# TPS.net
KiCad netlist of a schematic drawn in EAGLE
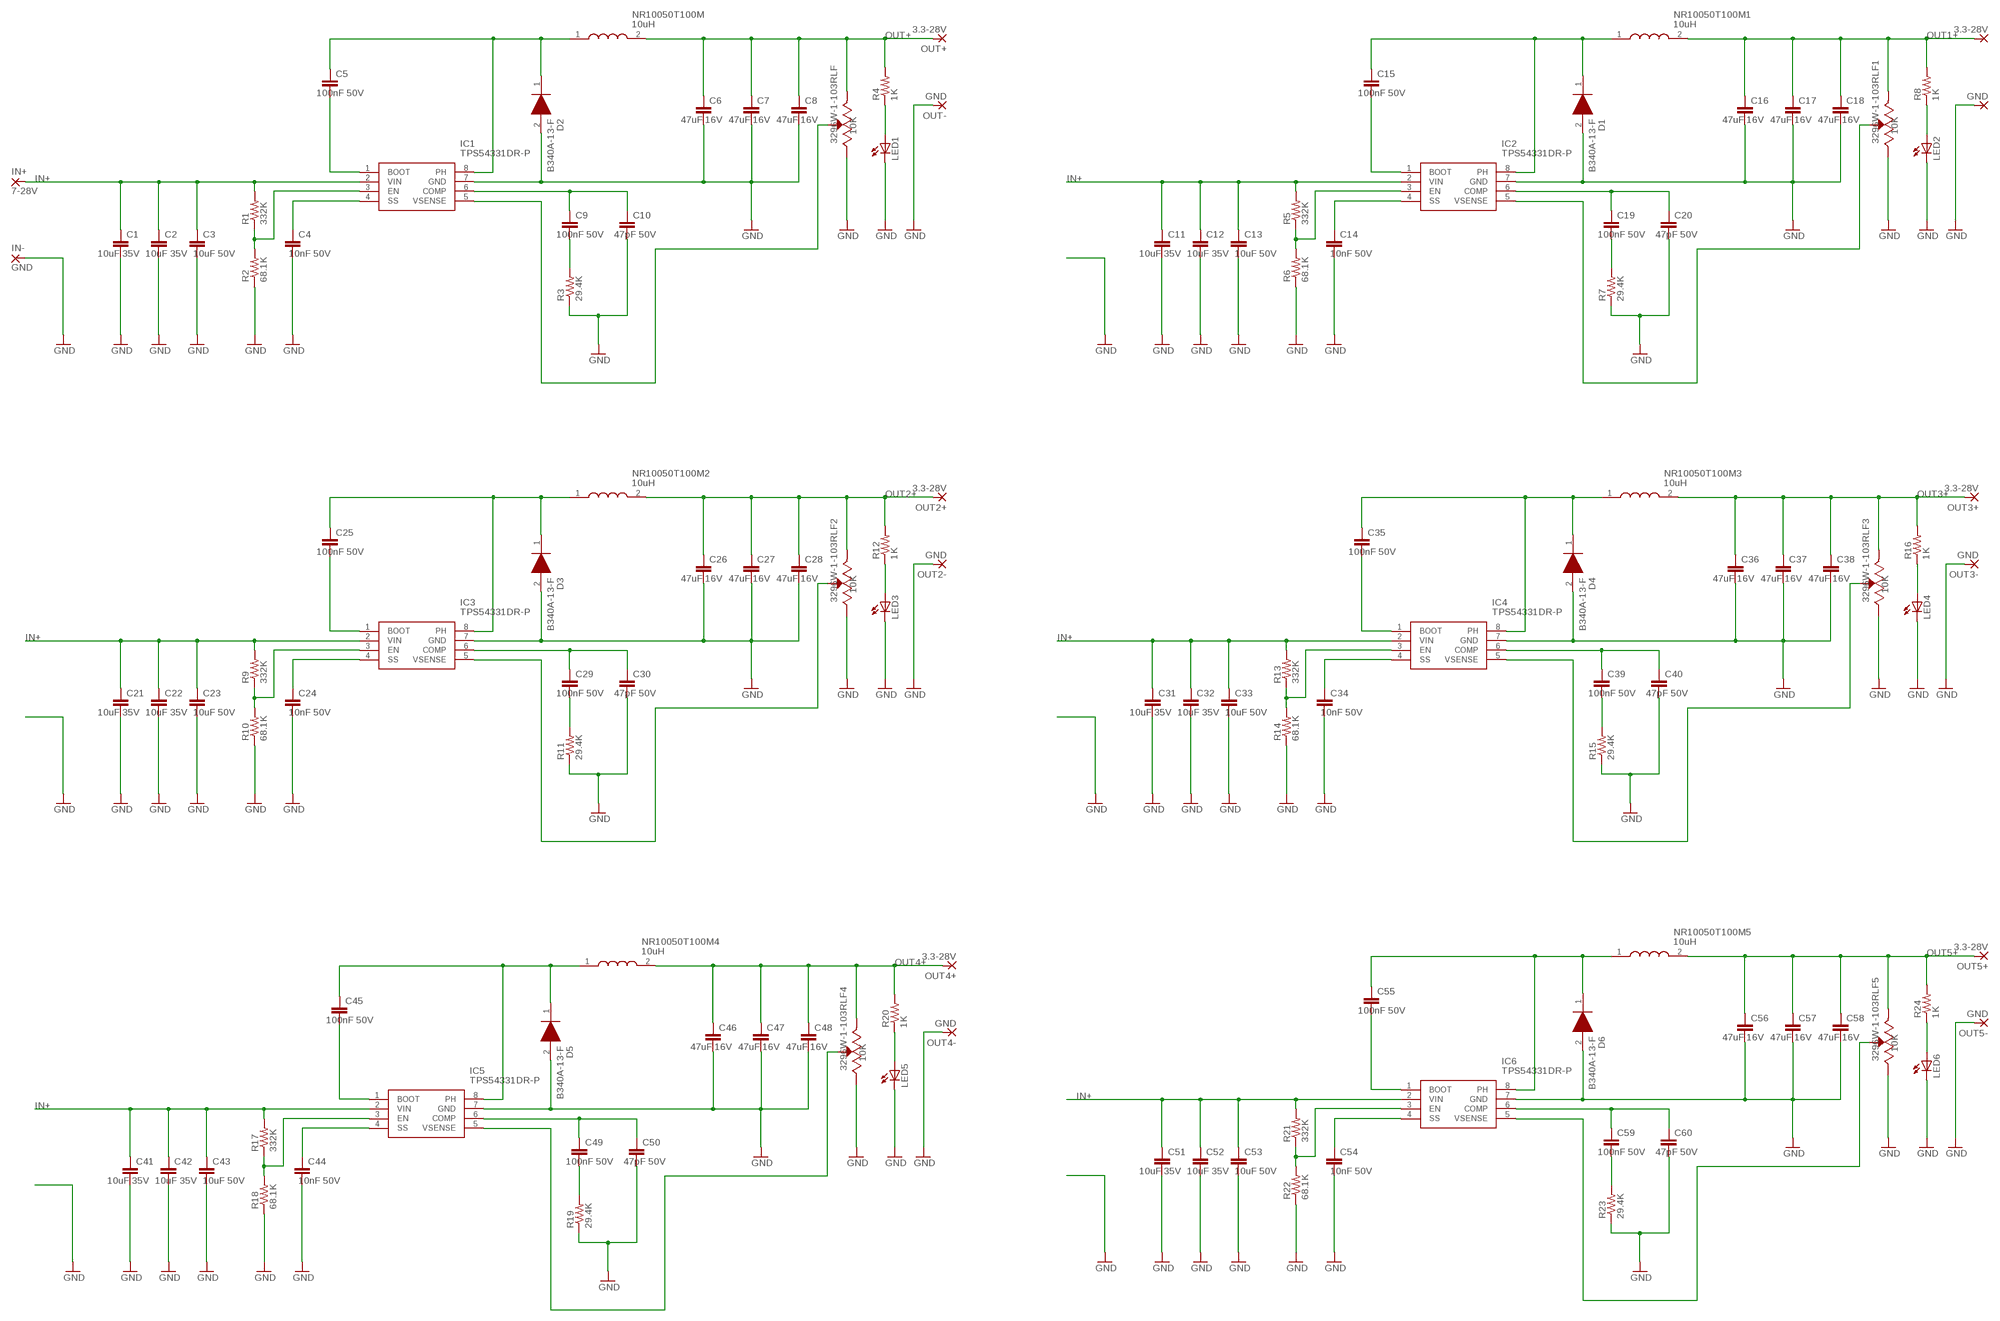
[diagram p0: schematic, sheet 1]

(export (version "E")
  (design (tool "Eeschema 10.0.6"))
  (components
    (comp (ref "3296W-1-103RLF")
      (value "10K")
      (footprint "eagle-import:TRIM_3296W-1-103RLF")
      (fields (field (name "MF") "Bourns") (field (name "MP") "3296W-1-103RLF"))
      (libsource (lib "eagle-import") (part "3296W-1-103RLF"))
    )
    (comp (ref "3296W-1-103RLF1")
      (value "10K")
      (footprint "eagle-import:TRIM_3296W-1-103RLF")
      (fields (field (name "MF") "Bourns") (field (name "MP") "3296W-1-103RLF"))
      (libsource (lib "eagle-import") (part "3296W-1-103RLF"))
    )
    (comp (ref "3296W-1-103RLF2")
      (value "10K")
      (footprint "eagle-import:TRIM_3296W-1-103RLF")
      (fields (field (name "MF") "Bourns") (field (name "MP") "3296W-1-103RLF"))
      (libsource (lib "eagle-import") (part "3296W-1-103RLF"))
    )
    (comp (ref "3296W-1-103RLF3")
      (value "10K")
      (footprint "eagle-import:TRIM_3296W-1-103RLF")
      (fields (field (name "MF") "Bourns") (field (name "MP") "3296W-1-103RLF"))
      (libsource (lib "eagle-import") (part "3296W-1-103RLF"))
    )
    (comp (ref "3296W-1-103RLF4")
      (value "10K")
      (footprint "eagle-import:TRIM_3296W-1-103RLF")
      (fields (field (name "MF") "Bourns") (field (name "MP") "3296W-1-103RLF"))
      (libsource (lib "eagle-import") (part "3296W-1-103RLF"))
    )
    (comp (ref "3296W-1-103RLF5")
      (value "10K")
      (footprint "eagle-import:TRIM_3296W-1-103RLF")
      (fields (field (name "MF") "Bourns") (field (name "MP") "3296W-1-103RLF"))
      (libsource (lib "eagle-import") (part "3296W-1-103RLF"))
    )
    (comp (ref "C1")
      (value "10uF 35V")
      (footprint "eagle-import:SPARKFUN_1206")
      (libsource (lib "eagle-import") (part "SPARKFUN_CAP1206"))
    )
    (comp (ref "C2")
      (value "10uF 35V")
      (footprint "eagle-import:SPARKFUN_1206")
      (libsource (lib "eagle-import") (part "SPARKFUN_CAP1206"))
    )
    (comp (ref "C3")
      (value "10uF 50V")
      (footprint "eagle-import:1206")
      (libsource (lib "eagle-import") (part "CAP1206"))
    )
    (comp (ref "C4")
      (value "10nF 50V")
      (footprint "eagle-import:SPARKFUN_1206")
      (libsource (lib "eagle-import") (part "SPARKFUN_CAP1206"))
    )
    (comp (ref "C5")
      (value "100nF 50V")
      (footprint "eagle-import:SPARKFUN_1206")
      (libsource (lib "eagle-import") (part "SPARKFUN_CAP1206"))
    )
    (comp (ref "C6")
      (value "47uF 16V")
      (footprint "eagle-import:SPARKFUN_1206")
      (libsource (lib "eagle-import") (part "SPARKFUN_CAP1206"))
    )
    (comp (ref "C7")
      (value "47uF 16V")
      (footprint "eagle-import:SPARKFUN_1206")
      (libsource (lib "eagle-import") (part "SPARKFUN_CAP1206"))
    )
    (comp (ref "C8")
      (value "47uF 16V")
      (footprint "eagle-import:SPARKFUN_1206")
      (libsource (lib "eagle-import") (part "SPARKFUN_CAP1206"))
    )
    (comp (ref "C9")
      (value "100nF 50V")
      (footprint "eagle-import:SPARKFUN_1206")
      (libsource (lib "eagle-import") (part "SPARKFUN_CAP1206"))
    )
    (comp (ref "C10")
      (value "47pF 50V")
      (footprint "eagle-import:SPARKFUN_1206")
      (libsource (lib "eagle-import") (part "SPARKFUN_CAP1206"))
    )
    (comp (ref "C11")
      (value "10uF 35V")
      (footprint "eagle-import:SPARKFUN_1206")
      (libsource (lib "eagle-import") (part "SPARKFUN_CAP1206"))
    )
    (comp (ref "C12")
      (value "10uF 35V")
      (footprint "eagle-import:SPARKFUN_1206")
      (libsource (lib "eagle-import") (part "SPARKFUN_CAP1206"))
    )
    (comp (ref "C13")
      (value "10uF 50V")
      (footprint "eagle-import:1206")
      (libsource (lib "eagle-import") (part "CAP1206"))
    )
    (comp (ref "C14")
      (value "10nF 50V")
      (footprint "eagle-import:SPARKFUN_1206")
      (libsource (lib "eagle-import") (part "SPARKFUN_CAP1206"))
    )
    (comp (ref "C15")
      (value "100nF 50V")
      (footprint "eagle-import:SPARKFUN_1206")
      (libsource (lib "eagle-import") (part "SPARKFUN_CAP1206"))
    )
    (comp (ref "C16")
      (value "47uF 16V")
      (footprint "eagle-import:SPARKFUN_1206")
      (libsource (lib "eagle-import") (part "SPARKFUN_CAP1206"))
    )
    (comp (ref "C17")
      (value "47uF 16V")
      (footprint "eagle-import:SPARKFUN_1206")
      (libsource (lib "eagle-import") (part "SPARKFUN_CAP1206"))
    )
    (comp (ref "C18")
      (value "47uF 16V")
      (footprint "eagle-import:SPARKFUN_1206")
      (libsource (lib "eagle-import") (part "SPARKFUN_CAP1206"))
    )
    (comp (ref "C19")
      (value "100nF 50V")
      (footprint "eagle-import:SPARKFUN_1206")
      (libsource (lib "eagle-import") (part "SPARKFUN_CAP1206"))
    )
    (comp (ref "C20")
      (value "47pF 50V")
      (footprint "eagle-import:SPARKFUN_1206")
      (libsource (lib "eagle-import") (part "SPARKFUN_CAP1206"))
    )
    (comp (ref "C21")
      (value "10uF 35V")
      (footprint "eagle-import:SPARKFUN_1206")
      (libsource (lib "eagle-import") (part "SPARKFUN_CAP1206"))
    )
    (comp (ref "C22")
      (value "10uF 35V")
      (footprint "eagle-import:SPARKFUN_1206")
      (libsource (lib "eagle-import") (part "SPARKFUN_CAP1206"))
    )
    (comp (ref "C23")
      (value "10uF 50V")
      (footprint "eagle-import:1206")
      (libsource (lib "eagle-import") (part "CAP1206"))
    )
    (comp (ref "C24")
      (value "10nF 50V")
      (footprint "eagle-import:SPARKFUN_1206")
      (libsource (lib "eagle-import") (part "SPARKFUN_CAP1206"))
    )
    (comp (ref "C25")
      (value "100nF 50V")
      (footprint "eagle-import:SPARKFUN_1206")
      (libsource (lib "eagle-import") (part "SPARKFUN_CAP1206"))
    )
    (comp (ref "C26")
      (value "47uF 16V")
      (footprint "eagle-import:SPARKFUN_1206")
      (libsource (lib "eagle-import") (part "SPARKFUN_CAP1206"))
    )
    (comp (ref "C27")
      (value "47uF 16V")
      (footprint "eagle-import:SPARKFUN_1206")
      (libsource (lib "eagle-import") (part "SPARKFUN_CAP1206"))
    )
    (comp (ref "C28")
      (value "47uF 16V")
      (footprint "eagle-import:SPARKFUN_1206")
      (libsource (lib "eagle-import") (part "SPARKFUN_CAP1206"))
    )
    (comp (ref "C29")
      (value "100nF 50V")
      (footprint "eagle-import:SPARKFUN_1206")
      (libsource (lib "eagle-import") (part "SPARKFUN_CAP1206"))
    )
    (comp (ref "C30")
      (value "47pF 50V")
      (footprint "eagle-import:SPARKFUN_1206")
      (libsource (lib "eagle-import") (part "SPARKFUN_CAP1206"))
    )
    (comp (ref "C31")
      (value "10uF 35V")
      (footprint "eagle-import:SPARKFUN_1206")
      (libsource (lib "eagle-import") (part "SPARKFUN_CAP1206"))
    )
    (comp (ref "C32")
      (value "10uF 35V")
      (footprint "eagle-import:SPARKFUN_1206")
      (libsource (lib "eagle-import") (part "SPARKFUN_CAP1206"))
    )
    (comp (ref "C33")
      (value "10uF 50V")
      (footprint "eagle-import:1206")
      (libsource (lib "eagle-import") (part "CAP1206"))
    )
    (comp (ref "C34")
      (value "10nF 50V")
      (footprint "eagle-import:SPARKFUN_1206")
      (libsource (lib "eagle-import") (part "SPARKFUN_CAP1206"))
    )
    (comp (ref "C35")
      (value "100nF 50V")
      (footprint "eagle-import:SPARKFUN_1206")
      (libsource (lib "eagle-import") (part "SPARKFUN_CAP1206"))
    )
    (comp (ref "C36")
      (value "47uF 16V")
      (footprint "eagle-import:SPARKFUN_1206")
      (libsource (lib "eagle-import") (part "SPARKFUN_CAP1206"))
    )
    (comp (ref "C37")
      (value "47uF 16V")
      (footprint "eagle-import:SPARKFUN_1206")
      (libsource (lib "eagle-import") (part "SPARKFUN_CAP1206"))
    )
    (comp (ref "C38")
      (value "47uF 16V")
      (footprint "eagle-import:SPARKFUN_1206")
      (libsource (lib "eagle-import") (part "SPARKFUN_CAP1206"))
    )
    (comp (ref "C39")
      (value "100nF 50V")
      (footprint "eagle-import:SPARKFUN_1206")
      (libsource (lib "eagle-import") (part "SPARKFUN_CAP1206"))
    )
    (comp (ref "C40")
      (value "47pF 50V")
      (footprint "eagle-import:SPARKFUN_1206")
      (libsource (lib "eagle-import") (part "SPARKFUN_CAP1206"))
    )
    (comp (ref "C41")
      (value "10uF 35V")
      (footprint "eagle-import:SPARKFUN_1206")
      (libsource (lib "eagle-import") (part "SPARKFUN_CAP1206"))
    )
    (comp (ref "C42")
      (value "10uF 35V")
      (footprint "eagle-import:SPARKFUN_1206")
      (libsource (lib "eagle-import") (part "SPARKFUN_CAP1206"))
    )
    (comp (ref "C43")
      (value "10uF 50V")
      (footprint "eagle-import:1206")
      (libsource (lib "eagle-import") (part "CAP1206"))
    )
    (comp (ref "C44")
      (value "10nF 50V")
      (footprint "eagle-import:SPARKFUN_1206")
      (libsource (lib "eagle-import") (part "SPARKFUN_CAP1206"))
    )
    (comp (ref "C45")
      (value "100nF 50V")
      (footprint "eagle-import:SPARKFUN_1206")
      (libsource (lib "eagle-import") (part "SPARKFUN_CAP1206"))
    )
    (comp (ref "C46")
      (value "47uF 16V")
      (footprint "eagle-import:SPARKFUN_1206")
      (libsource (lib "eagle-import") (part "SPARKFUN_CAP1206"))
    )
    (comp (ref "C47")
      (value "47uF 16V")
      (footprint "eagle-import:SPARKFUN_1206")
      (libsource (lib "eagle-import") (part "SPARKFUN_CAP1206"))
    )
    (comp (ref "C48")
      (value "47uF 16V")
      (footprint "eagle-import:SPARKFUN_1206")
      (libsource (lib "eagle-import") (part "SPARKFUN_CAP1206"))
    )
    (comp (ref "C49")
      (value "100nF 50V")
      (footprint "eagle-import:SPARKFUN_1206")
      (libsource (lib "eagle-import") (part "SPARKFUN_CAP1206"))
    )
    (comp (ref "C50")
      (value "47pF 50V")
      (footprint "eagle-import:SPARKFUN_1206")
      (libsource (lib "eagle-import") (part "SPARKFUN_CAP1206"))
    )
    (comp (ref "C51")
      (value "10uF 35V")
      (footprint "eagle-import:SPARKFUN_1206")
      (libsource (lib "eagle-import") (part "SPARKFUN_CAP1206"))
    )
    (comp (ref "C52")
      (value "10uF 35V")
      (footprint "eagle-import:SPARKFUN_1206")
      (libsource (lib "eagle-import") (part "SPARKFUN_CAP1206"))
    )
    (comp (ref "C53")
      (value "10uF 50V")
      (footprint "eagle-import:1206")
      (libsource (lib "eagle-import") (part "CAP1206"))
    )
    (comp (ref "C54")
      (value "10nF 50V")
      (footprint "eagle-import:SPARKFUN_1206")
      (libsource (lib "eagle-import") (part "SPARKFUN_CAP1206"))
    )
    (comp (ref "C55")
      (value "100nF 50V")
      (footprint "eagle-import:SPARKFUN_1206")
      (libsource (lib "eagle-import") (part "SPARKFUN_CAP1206"))
    )
    (comp (ref "C56")
      (value "47uF 16V")
      (footprint "eagle-import:SPARKFUN_1206")
      (libsource (lib "eagle-import") (part "SPARKFUN_CAP1206"))
    )
    (comp (ref "C57")
      (value "47uF 16V")
      (footprint "eagle-import:SPARKFUN_1206")
      (libsource (lib "eagle-import") (part "SPARKFUN_CAP1206"))
    )
    (comp (ref "C58")
      (value "47uF 16V")
      (footprint "eagle-import:SPARKFUN_1206")
      (libsource (lib "eagle-import") (part "SPARKFUN_CAP1206"))
    )
    (comp (ref "C59")
      (value "100nF 50V")
      (footprint "eagle-import:SPARKFUN_1206")
      (libsource (lib "eagle-import") (part "SPARKFUN_CAP1206"))
    )
    (comp (ref "C60")
      (value "47pF 50V")
      (footprint "eagle-import:SPARKFUN_1206")
      (libsource (lib "eagle-import") (part "SPARKFUN_CAP1206"))
    )
    (comp (ref "D1")
      (value "B340A-13-F")
      (footprint "eagle-import:DIOM5226X240N")
      (fields (field (name "MOUSER_PART_NUMBER") "621-B340A-F"))
      (libsource (lib "eagle-import") (part "B340A-13-F"))
    )
    (comp (ref "D2")
      (value "B340A-13-F")
      (footprint "eagle-import:DIOM5226X240N")
      (fields (field (name "MOUSER_PART_NUMBER") "621-B340A-F"))
      (libsource (lib "eagle-import") (part "B340A-13-F"))
    )
    (comp (ref "D3")
      (value "B340A-13-F")
      (footprint "eagle-import:DIOM5226X240N")
      (fields (field (name "MOUSER_PART_NUMBER") "621-B340A-F"))
      (libsource (lib "eagle-import") (part "B340A-13-F"))
    )
    (comp (ref "D4")
      (value "B340A-13-F")
      (footprint "eagle-import:DIOM5226X240N")
      (fields (field (name "MOUSER_PART_NUMBER") "621-B340A-F"))
      (libsource (lib "eagle-import") (part "B340A-13-F"))
    )
    (comp (ref "D5")
      (value "B340A-13-F")
      (footprint "eagle-import:DIOM5226X240N")
      (fields (field (name "MOUSER_PART_NUMBER") "621-B340A-F"))
      (libsource (lib "eagle-import") (part "B340A-13-F"))
    )
    (comp (ref "D6")
      (value "B340A-13-F")
      (footprint "eagle-import:DIOM5226X240N")
      (fields (field (name "MOUSER_PART_NUMBER") "621-B340A-F"))
      (libsource (lib "eagle-import") (part "B340A-13-F"))
    )
    (comp (ref "IC1")
      (value "TPS54331DR-P")
      (footprint "eagle-import:SOIC127P600X175-8N")
      (libsource (lib "eagle-import") (part "TPS54331DR-P"))
    )
    (comp (ref "IC2")
      (value "TPS54331DR-P")
      (footprint "eagle-import:SOIC127P600X175-8N")
      (libsource (lib "eagle-import") (part "TPS54331DR-P"))
    )
    (comp (ref "IC3")
      (value "TPS54331DR-P")
      (footprint "eagle-import:SOIC127P600X175-8N")
      (libsource (lib "eagle-import") (part "TPS54331DR-P"))
    )
    (comp (ref "IC4")
      (value "TPS54331DR-P")
      (footprint "eagle-import:SOIC127P600X175-8N")
      (libsource (lib "eagle-import") (part "TPS54331DR-P"))
    )
    (comp (ref "IC5")
      (value "TPS54331DR-P")
      (footprint "eagle-import:SOIC127P600X175-8N")
      (libsource (lib "eagle-import") (part "TPS54331DR-P"))
    )
    (comp (ref "IC6")
      (value "TPS54331DR-P")
      (footprint "eagle-import:SOIC127P600X175-8N")
      (libsource (lib "eagle-import") (part "TPS54331DR-P"))
    )
    (comp (ref "IN+")
      (value "7-28V")
      (footprint "eagle-import:5-2,5")
      (libsource (lib "eagle-import") (part "WIREPADSMD5-2,5"))
    )
    (comp (ref "IN-")
      (value "GND")
      (footprint "eagle-import:3,81_1,4")
      (libsource (lib "eagle-import") (part "WIREPAD3,81/1,4"))
    )
    (comp (ref "LED1")
      (value "SPARKFUN_LED1206")
      (footprint "eagle-import:SPARKFUN_LED-1206")
      (libsource (lib "eagle-import") (part "SPARKFUN_LED1206"))
    )
    (comp (ref "LED2")
      (value "SPARKFUN_LED1206")
      (footprint "eagle-import:SPARKFUN_LED-1206")
      (libsource (lib "eagle-import") (part "SPARKFUN_LED1206"))
    )
    (comp (ref "LED3")
      (value "SPARKFUN_LED1206")
      (footprint "eagle-import:SPARKFUN_LED-1206")
      (libsource (lib "eagle-import") (part "SPARKFUN_LED1206"))
    )
    (comp (ref "LED4")
      (value "SPARKFUN_LED1206")
      (footprint "eagle-import:SPARKFUN_LED-1206")
      (libsource (lib "eagle-import") (part "SPARKFUN_LED1206"))
    )
    (comp (ref "LED5")
      (value "SPARKFUN_LED1206")
      (footprint "eagle-import:SPARKFUN_LED-1206")
      (libsource (lib "eagle-import") (part "SPARKFUN_LED1206"))
    )
    (comp (ref "LED6")
      (value "SPARKFUN_LED1206")
      (footprint "eagle-import:SPARKFUN_LED-1206")
      (libsource (lib "eagle-import") (part "SPARKFUN_LED1206"))
    )
    (comp (ref "NR10050T100M")
      (value "10uH")
      (footprint "eagle-import:NR10050T100M")
      (fields
        (field (name "ARROW_PART_NUMBER") "NR10050T100M")
        (field (name "MOUSER_PART_NUMBER") "963-NR10050T100M")
      )
      (libsource (lib "eagle-import") (part "NR10050T100M"))
    )
    (comp (ref "NR10050T100M1")
      (value "10uH")
      (footprint "eagle-import:NR10050T100M")
      (fields
        (field (name "ARROW_PART_NUMBER") "NR10050T100M")
        (field (name "MOUSER_PART_NUMBER") "963-NR10050T100M")
      )
      (libsource (lib "eagle-import") (part "NR10050T100M"))
    )
    (comp (ref "NR10050T100M2")
      (value "10uH")
      (footprint "eagle-import:NR10050T100M")
      (fields
        (field (name "ARROW_PART_NUMBER") "NR10050T100M")
        (field (name "MOUSER_PART_NUMBER") "963-NR10050T100M")
      )
      (libsource (lib "eagle-import") (part "NR10050T100M"))
    )
    (comp (ref "NR10050T100M3")
      (value "10uH")
      (footprint "eagle-import:NR10050T100M")
      (fields
        (field (name "ARROW_PART_NUMBER") "NR10050T100M")
        (field (name "MOUSER_PART_NUMBER") "963-NR10050T100M")
      )
      (libsource (lib "eagle-import") (part "NR10050T100M"))
    )
    (comp (ref "NR10050T100M4")
      (value "10uH")
      (footprint "eagle-import:NR10050T100M")
      (fields
        (field (name "ARROW_PART_NUMBER") "NR10050T100M")
        (field (name "MOUSER_PART_NUMBER") "963-NR10050T100M")
      )
      (libsource (lib "eagle-import") (part "NR10050T100M"))
    )
    (comp (ref "NR10050T100M5")
      (value "10uH")
      (footprint "eagle-import:NR10050T100M")
      (fields
        (field (name "ARROW_PART_NUMBER") "NR10050T100M")
        (field (name "MOUSER_PART_NUMBER") "963-NR10050T100M")
      )
      (libsource (lib "eagle-import") (part "NR10050T100M"))
    )
    (comp (ref "OUT+")
      (value "3.3-28V")
      (footprint "eagle-import:5-2,5")
      (libsource (lib "eagle-import") (part "WIREPADSMD5-2,5"))
    )
    (comp (ref "OUT-")
      (value "GND")
      (footprint "eagle-import:3,81_1,4")
      (libsource (lib "eagle-import") (part "WIREPAD3,81/1,4"))
    )
    (comp (ref "OUT1+")
      (value "3.3-28V")
      (footprint "eagle-import:5-2,5")
      (libsource (lib "eagle-import") (part "WIREPADSMD5-2,5"))
    )
    (comp (ref "OUT1-")
      (value "GND")
      (footprint "eagle-import:3,81_1,4")
      (libsource (lib "eagle-import") (part "WIREPAD3,81/1,4"))
    )
    (comp (ref "OUT2+")
      (value "3.3-28V")
      (footprint "eagle-import:5-2,5")
      (libsource (lib "eagle-import") (part "WIREPADSMD5-2,5"))
    )
    (comp (ref "OUT2-")
      (value "GND")
      (footprint "eagle-import:3,81_1,4")
      (libsource (lib "eagle-import") (part "WIREPAD3,81/1,4"))
    )
    (comp (ref "OUT3+")
      (value "3.3-28V")
      (footprint "eagle-import:5-2,5")
      (libsource (lib "eagle-import") (part "WIREPADSMD5-2,5"))
    )
    (comp (ref "OUT3-")
      (value "GND")
      (footprint "eagle-import:3,81_1,4")
      (libsource (lib "eagle-import") (part "WIREPAD3,81/1,4"))
    )
    (comp (ref "OUT4+")
      (value "3.3-28V")
      (footprint "eagle-import:5-2,5")
      (libsource (lib "eagle-import") (part "WIREPADSMD5-2,5"))
    )
    (comp (ref "OUT4-")
      (value "GND")
      (footprint "eagle-import:3,81_1,4")
      (libsource (lib "eagle-import") (part "WIREPAD3,81/1,4"))
    )
    (comp (ref "OUT5+")
      (value "3.3-28V")
      (footprint "eagle-import:5-2,5")
      (libsource (lib "eagle-import") (part "WIREPADSMD5-2,5"))
    )
    (comp (ref "OUT5-")
      (value "GND")
      (footprint "eagle-import:3,81_1,4")
      (libsource (lib "eagle-import") (part "WIREPAD3,81/1,4"))
    )
    (comp (ref "R1")
      (value "332K")
      (footprint "eagle-import:M1206")
      (libsource (lib "eagle-import") (part "R-US_M1206"))
    )
    (comp (ref "R2")
      (value "68.1K")
      (footprint "eagle-import:M1206")
      (libsource (lib "eagle-import") (part "R-US_M1206"))
    )
    (comp (ref "R3")
      (value "29.4K")
      (footprint "eagle-import:M1206")
      (libsource (lib "eagle-import") (part "R-US_M1206"))
    )
    (comp (ref "R4")
      (value "1K")
      (footprint "eagle-import:M1206")
      (libsource (lib "eagle-import") (part "R-US_M1206"))
    )
    (comp (ref "R5")
      (value "332K")
      (footprint "eagle-import:M1206")
      (libsource (lib "eagle-import") (part "R-US_M1206"))
    )
    (comp (ref "R6")
      (value "68.1K")
      (footprint "eagle-import:M1206")
      (libsource (lib "eagle-import") (part "R-US_M1206"))
    )
    (comp (ref "R7")
      (value "29.4K")
      (footprint "eagle-import:M1206")
      (libsource (lib "eagle-import") (part "R-US_M1206"))
    )
    (comp (ref "R8")
      (value "1K")
      (footprint "eagle-import:M1206")
      (libsource (lib "eagle-import") (part "R-US_M1206"))
    )
    (comp (ref "R9")
      (value "332K")
      (footprint "eagle-import:M1206")
      (libsource (lib "eagle-import") (part "R-US_M1206"))
    )
    (comp (ref "R10")
      (value "68.1K")
      (footprint "eagle-import:M1206")
      (libsource (lib "eagle-import") (part "R-US_M1206"))
    )
    (comp (ref "R11")
      (value "29.4K")
      (footprint "eagle-import:M1206")
      (libsource (lib "eagle-import") (part "R-US_M1206"))
    )
    (comp (ref "R12")
      (value "1K")
      (footprint "eagle-import:M1206")
      (libsource (lib "eagle-import") (part "R-US_M1206"))
    )
    (comp (ref "R13")
      (value "332K")
      (footprint "eagle-import:M1206")
      (libsource (lib "eagle-import") (part "R-US_M1206"))
    )
    (comp (ref "R14")
      (value "68.1K")
      (footprint "eagle-import:M1206")
      (libsource (lib "eagle-import") (part "R-US_M1206"))
    )
    (comp (ref "R15")
      (value "29.4K")
      (footprint "eagle-import:M1206")
      (libsource (lib "eagle-import") (part "R-US_M1206"))
    )
    (comp (ref "R16")
      (value "1K")
      (footprint "eagle-import:M1206")
      (libsource (lib "eagle-import") (part "R-US_M1206"))
    )
    (comp (ref "R17")
      (value "332K")
      (footprint "eagle-import:M1206")
      (libsource (lib "eagle-import") (part "R-US_M1206"))
    )
    (comp (ref "R18")
      (value "68.1K")
      (footprint "eagle-import:M1206")
      (libsource (lib "eagle-import") (part "R-US_M1206"))
    )
    (comp (ref "R19")
      (value "29.4K")
      (footprint "eagle-import:M1206")
      (libsource (lib "eagle-import") (part "R-US_M1206"))
    )
    (comp (ref "R20")
      (value "1K")
      (footprint "eagle-import:M1206")
      (libsource (lib "eagle-import") (part "R-US_M1206"))
    )
    (comp (ref "R21")
      (value "332K")
      (footprint "eagle-import:M1206")
      (libsource (lib "eagle-import") (part "R-US_M1206"))
    )
    (comp (ref "R22")
      (value "68.1K")
      (footprint "eagle-import:M1206")
      (libsource (lib "eagle-import") (part "R-US_M1206"))
    )
    (comp (ref "R23")
      (value "29.4K")
      (footprint "eagle-import:M1206")
      (libsource (lib "eagle-import") (part "R-US_M1206"))
    )
    (comp (ref "R24")
      (value "1K")
      (footprint "eagle-import:M1206")
      (libsource (lib "eagle-import") (part "R-US_M1206"))
    )
  )
  (nets
    (net (code "1") (name "/IN+") (class "Default")
      (node (ref "C1") (pin "1") (pinfunction "1_1") (pintype "passive"))
      (node (ref "C11") (pin "1") (pinfunction "1_1") (pintype "passive"))
      (node (ref "C12") (pin "1") (pinfunction "1_1") (pintype "passive"))
      (node (ref "C13") (pin "1") (pinfunction "1_1") (pintype "passive"))
      (node (ref "C2") (pin "1") (pinfunction "1_1") (pintype "passive"))
      (node (ref "C21") (pin "1") (pinfunction "1_1") (pintype "passive"))
      (node (ref "C22") (pin "1") (pinfunction "1_1") (pintype "passive"))
      (node (ref "C23") (pin "1") (pinfunction "1_1") (pintype "passive"))
      (node (ref "C3") (pin "1") (pinfunction "1_1") (pintype "passive"))
      (node (ref "C31") (pin "1") (pinfunction "1_1") (pintype "passive"))
      (node (ref "C32") (pin "1") (pinfunction "1_1") (pintype "passive"))
      (node (ref "C33") (pin "1") (pinfunction "1_1") (pintype "passive"))
      (node (ref "C41") (pin "1") (pinfunction "1_1") (pintype "passive"))
      (node (ref "C42") (pin "1") (pinfunction "1_1") (pintype "passive"))
      (node (ref "C43") (pin "1") (pinfunction "1_1") (pintype "passive"))
      (node (ref "C51") (pin "1") (pinfunction "1_1") (pintype "passive"))
      (node (ref "C52") (pin "1") (pinfunction "1_1") (pintype "passive"))
      (node (ref "C53") (pin "1") (pinfunction "1_1") (pintype "passive"))
      (node (ref "IC1") (pin "2") (pinfunction "VIN_2") (pintype "bidirectional"))
      (node (ref "IC2") (pin "2") (pinfunction "VIN_2") (pintype "bidirectional"))
      (node (ref "IC3") (pin "2") (pinfunction "VIN_2") (pintype "bidirectional"))
      (node (ref "IC4") (pin "2") (pinfunction "VIN_2") (pintype "bidirectional"))
      (node (ref "IC5") (pin "2") (pinfunction "VIN_2") (pintype "bidirectional"))
      (node (ref "IC6") (pin "2") (pinfunction "VIN_2") (pintype "bidirectional"))
      (node (ref "IN+") (pin "1") (pinfunction "P_1") (pintype "passive"))
      (node (ref "R1") (pin "2") (pinfunction "2_2") (pintype "passive"))
      (node (ref "R13") (pin "2") (pinfunction "2_2") (pintype "passive"))
      (node (ref "R17") (pin "2") (pinfunction "2_2") (pintype "passive"))
      (node (ref "R21") (pin "2") (pinfunction "2_2") (pintype "passive"))
      (node (ref "R5") (pin "2") (pinfunction "2_2") (pintype "passive"))
      (node (ref "R9") (pin "2") (pinfunction "2_2") (pintype "passive"))
    )
    (net (code "2") (name "/OUT+") (class "Default")
      (node (ref "3296W-1-103RLF") (pin "3") (pinfunction "CW_3") (pintype "passive"))
      (node (ref "C6") (pin "1") (pinfunction "1_1") (pintype "passive"))
      (node (ref "C7") (pin "1") (pinfunction "1_1") (pintype "passive"))
      (node (ref "C8") (pin "1") (pinfunction "1_1") (pintype "passive"))
      (node (ref "NR10050T100M") (pin "2") (pinfunction "2_2") (pintype "bidirectional"))
      (node (ref "OUT+") (pin "1") (pinfunction "P_1") (pintype "passive"))
      (node (ref "R4") (pin "2") (pinfunction "2_2") (pintype "passive"))
    )
    (net (code "3") (name "/OUT1+") (class "Default")
      (node (ref "3296W-1-103RLF1") (pin "3") (pinfunction "CW_3") (pintype "passive"))
      (node (ref "C16") (pin "1") (pinfunction "1_1") (pintype "passive"))
      (node (ref "C17") (pin "1") (pinfunction "1_1") (pintype "passive"))
      (node (ref "C18") (pin "1") (pinfunction "1_1") (pintype "passive"))
      (node (ref "NR10050T100M1") (pin "2") (pinfunction "2_2") (pintype "bidirectional"))
      (node (ref "OUT1+") (pin "1") (pinfunction "P_1") (pintype "passive"))
      (node (ref "R8") (pin "2") (pinfunction "2_2") (pintype "passive"))
    )
    (net (code "4") (name "/OUT2+") (class "Default")
      (node (ref "3296W-1-103RLF2") (pin "3") (pinfunction "CW_3") (pintype "passive"))
      (node (ref "C26") (pin "1") (pinfunction "1_1") (pintype "passive"))
      (node (ref "C27") (pin "1") (pinfunction "1_1") (pintype "passive"))
      (node (ref "C28") (pin "1") (pinfunction "1_1") (pintype "passive"))
      (node (ref "NR10050T100M2") (pin "2") (pinfunction "2_2") (pintype "bidirectional"))
      (node (ref "OUT2+") (pin "1") (pinfunction "P_1") (pintype "passive"))
      (node (ref "R12") (pin "2") (pinfunction "2_2") (pintype "passive"))
    )
    (net (code "5") (name "/OUT3+") (class "Default")
      (node (ref "3296W-1-103RLF3") (pin "3") (pinfunction "CW_3") (pintype "passive"))
      (node (ref "C36") (pin "1") (pinfunction "1_1") (pintype "passive"))
      (node (ref "C37") (pin "1") (pinfunction "1_1") (pintype "passive"))
      (node (ref "C38") (pin "1") (pinfunction "1_1") (pintype "passive"))
      (node (ref "NR10050T100M3") (pin "2") (pinfunction "2_2") (pintype "bidirectional"))
      (node (ref "OUT3+") (pin "1") (pinfunction "P_1") (pintype "passive"))
      (node (ref "R16") (pin "2") (pinfunction "2_2") (pintype "passive"))
    )
    (net (code "6") (name "/OUT4+") (class "Default")
      (node (ref "3296W-1-103RLF4") (pin "3") (pinfunction "CW_3") (pintype "passive"))
      (node (ref "C46") (pin "1") (pinfunction "1_1") (pintype "passive"))
      (node (ref "C47") (pin "1") (pinfunction "1_1") (pintype "passive"))
      (node (ref "C48") (pin "1") (pinfunction "1_1") (pintype "passive"))
      (node (ref "NR10050T100M4") (pin "2") (pinfunction "2_2") (pintype "bidirectional"))
      (node (ref "OUT4+") (pin "1") (pinfunction "P_1") (pintype "passive"))
      (node (ref "R20") (pin "2") (pinfunction "2_2") (pintype "passive"))
    )
    (net (code "7") (name "/OUT5+") (class "Default")
      (node (ref "3296W-1-103RLF5") (pin "3") (pinfunction "CW_3") (pintype "passive"))
      (node (ref "C56") (pin "1") (pinfunction "1_1") (pintype "passive"))
      (node (ref "C57") (pin "1") (pinfunction "1_1") (pintype "passive"))
      (node (ref "C58") (pin "1") (pinfunction "1_1") (pintype "passive"))
      (node (ref "NR10050T100M5") (pin "2") (pinfunction "2_2") (pintype "bidirectional"))
      (node (ref "OUT5+") (pin "1") (pinfunction "P_1") (pintype "passive"))
      (node (ref "R24") (pin "2") (pinfunction "2_2") (pintype "passive"))
    )
    (net (code "8") (name "GND") (class "Default")
      (node (ref "3296W-1-103RLF") (pin "1") (pinfunction "CCW_1") (pintype "passive"))
      (node (ref "3296W-1-103RLF1") (pin "1") (pinfunction "CCW_1") (pintype "passive"))
      (node (ref "3296W-1-103RLF2") (pin "1") (pinfunction "CCW_1") (pintype "passive"))
      (node (ref "3296W-1-103RLF3") (pin "1") (pinfunction "CCW_1") (pintype "passive"))
      (node (ref "3296W-1-103RLF4") (pin "1") (pinfunction "CCW_1") (pintype "passive"))
      (node (ref "3296W-1-103RLF5") (pin "1") (pinfunction "CCW_1") (pintype "passive"))
      (node (ref "C1") (pin "2") (pinfunction "2_2") (pintype "passive"))
      (node (ref "C10") (pin "2") (pinfunction "2_2") (pintype "passive"))
      (node (ref "C11") (pin "2") (pinfunction "2_2") (pintype "passive"))
      (node (ref "C12") (pin "2") (pinfunction "2_2") (pintype "passive"))
      (node (ref "C13") (pin "2") (pinfunction "2_2") (pintype "passive"))
      (node (ref "C14") (pin "2") (pinfunction "2_2") (pintype "passive"))
      (node (ref "C16") (pin "2") (pinfunction "2_2") (pintype "passive"))
      (node (ref "C17") (pin "2") (pinfunction "2_2") (pintype "passive"))
      (node (ref "C18") (pin "2") (pinfunction "2_2") (pintype "passive"))
      (node (ref "C2") (pin "2") (pinfunction "2_2") (pintype "passive"))
      (node (ref "C20") (pin "2") (pinfunction "2_2") (pintype "passive"))
      (node (ref "C21") (pin "2") (pinfunction "2_2") (pintype "passive"))
      (node (ref "C22") (pin "2") (pinfunction "2_2") (pintype "passive"))
      (node (ref "C23") (pin "2") (pinfunction "2_2") (pintype "passive"))
      (node (ref "C24") (pin "2") (pinfunction "2_2") (pintype "passive"))
      (node (ref "C26") (pin "2") (pinfunction "2_2") (pintype "passive"))
      (node (ref "C27") (pin "2") (pinfunction "2_2") (pintype "passive"))
      (node (ref "C28") (pin "2") (pinfunction "2_2") (pintype "passive"))
      (node (ref "C3") (pin "2") (pinfunction "2_2") (pintype "passive"))
      (node (ref "C30") (pin "2") (pinfunction "2_2") (pintype "passive"))
      (node (ref "C31") (pin "2") (pinfunction "2_2") (pintype "passive"))
      (node (ref "C32") (pin "2") (pinfunction "2_2") (pintype "passive"))
      (node (ref "C33") (pin "2") (pinfunction "2_2") (pintype "passive"))
      (node (ref "C34") (pin "2") (pinfunction "2_2") (pintype "passive"))
      (node (ref "C36") (pin "2") (pinfunction "2_2") (pintype "passive"))
      (node (ref "C37") (pin "2") (pinfunction "2_2") (pintype "passive"))
      (node (ref "C38") (pin "2") (pinfunction "2_2") (pintype "passive"))
      (node (ref "C4") (pin "2") (pinfunction "2_2") (pintype "passive"))
      (node (ref "C40") (pin "2") (pinfunction "2_2") (pintype "passive"))
      (node (ref "C41") (pin "2") (pinfunction "2_2") (pintype "passive"))
      (node (ref "C42") (pin "2") (pinfunction "2_2") (pintype "passive"))
      (node (ref "C43") (pin "2") (pinfunction "2_2") (pintype "passive"))
      (node (ref "C44") (pin "2") (pinfunction "2_2") (pintype "passive"))
      (node (ref "C46") (pin "2") (pinfunction "2_2") (pintype "passive"))
      (node (ref "C47") (pin "2") (pinfunction "2_2") (pintype "passive"))
      (node (ref "C48") (pin "2") (pinfunction "2_2") (pintype "passive"))
      (node (ref "C50") (pin "2") (pinfunction "2_2") (pintype "passive"))
      (node (ref "C51") (pin "2") (pinfunction "2_2") (pintype "passive"))
      (node (ref "C52") (pin "2") (pinfunction "2_2") (pintype "passive"))
      (node (ref "C53") (pin "2") (pinfunction "2_2") (pintype "passive"))
      (node (ref "C54") (pin "2") (pinfunction "2_2") (pintype "passive"))
      (node (ref "C56") (pin "2") (pinfunction "2_2") (pintype "passive"))
      (node (ref "C57") (pin "2") (pinfunction "2_2") (pintype "passive"))
      (node (ref "C58") (pin "2") (pinfunction "2_2") (pintype "passive"))
      (node (ref "C6") (pin "2") (pinfunction "2_2") (pintype "passive"))
      (node (ref "C60") (pin "2") (pinfunction "2_2") (pintype "passive"))
      (node (ref "C7") (pin "2") (pinfunction "2_2") (pintype "passive"))
      (node (ref "C8") (pin "2") (pinfunction "2_2") (pintype "passive"))
      (node (ref "D1") (pin "2") (pinfunction "A_2") (pintype "bidirectional"))
      (node (ref "D2") (pin "2") (pinfunction "A_2") (pintype "bidirectional"))
      (node (ref "D3") (pin "2") (pinfunction "A_2") (pintype "bidirectional"))
      (node (ref "D4") (pin "2") (pinfunction "A_2") (pintype "bidirectional"))
      (node (ref "D5") (pin "2") (pinfunction "A_2") (pintype "bidirectional"))
      (node (ref "D6") (pin "2") (pinfunction "A_2") (pintype "bidirectional"))
      (node (ref "IC1") (pin "7") (pinfunction "GND_7") (pintype "bidirectional"))
      (node (ref "IC2") (pin "7") (pinfunction "GND_7") (pintype "bidirectional"))
      (node (ref "IC3") (pin "7") (pinfunction "GND_7") (pintype "bidirectional"))
      (node (ref "IC4") (pin "7") (pinfunction "GND_7") (pintype "bidirectional"))
      (node (ref "IC5") (pin "7") (pinfunction "GND_7") (pintype "bidirectional"))
      (node (ref "IC6") (pin "7") (pinfunction "GND_7") (pintype "bidirectional"))
      (node (ref "IN-") (pin "1") (pinfunction "P_1") (pintype "passive"))
      (node (ref "LED1") (pin "C") (pinfunction "C_C") (pintype "passive"))
      (node (ref "LED2") (pin "C") (pinfunction "C_C") (pintype "passive"))
      (node (ref "LED3") (pin "C") (pinfunction "C_C") (pintype "passive"))
      (node (ref "LED4") (pin "C") (pinfunction "C_C") (pintype "passive"))
      (node (ref "LED5") (pin "C") (pinfunction "C_C") (pintype "passive"))
      (node (ref "LED6") (pin "C") (pinfunction "C_C") (pintype "passive"))
      (node (ref "OUT-") (pin "1") (pinfunction "P_1") (pintype "passive"))
      (node (ref "OUT1-") (pin "1") (pinfunction "P_1") (pintype "passive"))
      (node (ref "OUT2-") (pin "1") (pinfunction "P_1") (pintype "passive"))
      (node (ref "OUT3-") (pin "1") (pinfunction "P_1") (pintype "passive"))
      (node (ref "OUT4-") (pin "1") (pinfunction "P_1") (pintype "passive"))
      (node (ref "OUT5-") (pin "1") (pinfunction "P_1") (pintype "passive"))
      (node (ref "R10") (pin "1") (pinfunction "1_1") (pintype "passive"))
      (node (ref "R11") (pin "1") (pinfunction "1_1") (pintype "passive"))
      (node (ref "R14") (pin "1") (pinfunction "1_1") (pintype "passive"))
      (node (ref "R15") (pin "1") (pinfunction "1_1") (pintype "passive"))
      (node (ref "R18") (pin "1") (pinfunction "1_1") (pintype "passive"))
      (node (ref "R19") (pin "1") (pinfunction "1_1") (pintype "passive"))
      (node (ref "R2") (pin "1") (pinfunction "1_1") (pintype "passive"))
      (node (ref "R22") (pin "1") (pinfunction "1_1") (pintype "passive"))
      (node (ref "R23") (pin "1") (pinfunction "1_1") (pintype "passive"))
      (node (ref "R3") (pin "1") (pinfunction "1_1") (pintype "passive"))
      (node (ref "R6") (pin "1") (pinfunction "1_1") (pintype "passive"))
      (node (ref "R7") (pin "1") (pinfunction "1_1") (pintype "passive"))
    )
    (net (code "9") (name "Net-(3296W-1-103RLF-WIPER)") (class "Default")
      (node (ref "3296W-1-103RLF") (pin "2") (pinfunction "WIPER_2") (pintype "passive"))
      (node (ref "IC1") (pin "5") (pinfunction "VSENSE_5") (pintype "bidirectional"))
    )
    (net (code "10") (name "Net-(3296W-1-103RLF1-WIPER)") (class "Default")
      (node (ref "3296W-1-103RLF1") (pin "2") (pinfunction "WIPER_2") (pintype "passive"))
      (node (ref "IC2") (pin "5") (pinfunction "VSENSE_5") (pintype "bidirectional"))
    )
    (net (code "11") (name "Net-(3296W-1-103RLF2-WIPER)") (class "Default")
      (node (ref "3296W-1-103RLF2") (pin "2") (pinfunction "WIPER_2") (pintype "passive"))
      (node (ref "IC3") (pin "5") (pinfunction "VSENSE_5") (pintype "bidirectional"))
    )
    (net (code "12") (name "Net-(3296W-1-103RLF3-WIPER)") (class "Default")
      (node (ref "3296W-1-103RLF3") (pin "2") (pinfunction "WIPER_2") (pintype "passive"))
      (node (ref "IC4") (pin "5") (pinfunction "VSENSE_5") (pintype "bidirectional"))
    )
    (net (code "13") (name "Net-(3296W-1-103RLF4-WIPER)") (class "Default")
      (node (ref "3296W-1-103RLF4") (pin "2") (pinfunction "WIPER_2") (pintype "passive"))
      (node (ref "IC5") (pin "5") (pinfunction "VSENSE_5") (pintype "bidirectional"))
    )
    (net (code "14") (name "Net-(3296W-1-103RLF5-WIPER)") (class "Default")
      (node (ref "3296W-1-103RLF5") (pin "2") (pinfunction "WIPER_2") (pintype "passive"))
      (node (ref "IC6") (pin "5") (pinfunction "VSENSE_5") (pintype "bidirectional"))
    )
    (net (code "15") (name "Net-(C9-Pad2)") (class "Default")
      (node (ref "C9") (pin "2") (pinfunction "2_2") (pintype "passive"))
      (node (ref "R3") (pin "2") (pinfunction "2_2") (pintype "passive"))
    )
    (net (code "16") (name "Net-(C19-Pad2)") (class "Default")
      (node (ref "C19") (pin "2") (pinfunction "2_2") (pintype "passive"))
      (node (ref "R7") (pin "2") (pinfunction "2_2") (pintype "passive"))
    )
    (net (code "17") (name "Net-(C29-Pad2)") (class "Default")
      (node (ref "C29") (pin "2") (pinfunction "2_2") (pintype "passive"))
      (node (ref "R11") (pin "2") (pinfunction "2_2") (pintype "passive"))
    )
    (net (code "18") (name "Net-(C39-Pad2)") (class "Default")
      (node (ref "C39") (pin "2") (pinfunction "2_2") (pintype "passive"))
      (node (ref "R15") (pin "2") (pinfunction "2_2") (pintype "passive"))
    )
    (net (code "19") (name "Net-(C49-Pad2)") (class "Default")
      (node (ref "C49") (pin "2") (pinfunction "2_2") (pintype "passive"))
      (node (ref "R19") (pin "2") (pinfunction "2_2") (pintype "passive"))
    )
    (net (code "20") (name "Net-(C59-Pad2)") (class "Default")
      (node (ref "C59") (pin "2") (pinfunction "2_2") (pintype "passive"))
      (node (ref "R23") (pin "2") (pinfunction "2_2") (pintype "passive"))
    )
    (net (code "21") (name "Net-(D1-K)") (class "Default")
      (node (ref "C15") (pin "1") (pinfunction "1_1") (pintype "passive"))
      (node (ref "D1") (pin "1") (pinfunction "K_1") (pintype "bidirectional"))
      (node (ref "IC2") (pin "8") (pinfunction "PH_8") (pintype "bidirectional"))
      (node (ref "NR10050T100M1") (pin "1") (pinfunction "1_1") (pintype "bidirectional"))
    )
    (net (code "22") (name "Net-(D2-K)") (class "Default")
      (node (ref "C5") (pin "1") (pinfunction "1_1") (pintype "passive"))
      (node (ref "D2") (pin "1") (pinfunction "K_1") (pintype "bidirectional"))
      (node (ref "IC1") (pin "8") (pinfunction "PH_8") (pintype "bidirectional"))
      (node (ref "NR10050T100M") (pin "1") (pinfunction "1_1") (pintype "bidirectional"))
    )
    (net (code "23") (name "Net-(D3-K)") (class "Default")
      (node (ref "C25") (pin "1") (pinfunction "1_1") (pintype "passive"))
      (node (ref "D3") (pin "1") (pinfunction "K_1") (pintype "bidirectional"))
      (node (ref "IC3") (pin "8") (pinfunction "PH_8") (pintype "bidirectional"))
      (node (ref "NR10050T100M2") (pin "1") (pinfunction "1_1") (pintype "bidirectional"))
    )
    (net (code "24") (name "Net-(D4-K)") (class "Default")
      (node (ref "C35") (pin "1") (pinfunction "1_1") (pintype "passive"))
      (node (ref "D4") (pin "1") (pinfunction "K_1") (pintype "bidirectional"))
      (node (ref "IC4") (pin "8") (pinfunction "PH_8") (pintype "bidirectional"))
      (node (ref "NR10050T100M3") (pin "1") (pinfunction "1_1") (pintype "bidirectional"))
    )
    (net (code "25") (name "Net-(D5-K)") (class "Default")
      (node (ref "C45") (pin "1") (pinfunction "1_1") (pintype "passive"))
      (node (ref "D5") (pin "1") (pinfunction "K_1") (pintype "bidirectional"))
      (node (ref "IC5") (pin "8") (pinfunction "PH_8") (pintype "bidirectional"))
      (node (ref "NR10050T100M4") (pin "1") (pinfunction "1_1") (pintype "bidirectional"))
    )
    (net (code "26") (name "Net-(D6-K)") (class "Default")
      (node (ref "C55") (pin "1") (pinfunction "1_1") (pintype "passive"))
      (node (ref "D6") (pin "1") (pinfunction "K_1") (pintype "bidirectional"))
      (node (ref "IC6") (pin "8") (pinfunction "PH_8") (pintype "bidirectional"))
      (node (ref "NR10050T100M5") (pin "1") (pinfunction "1_1") (pintype "bidirectional"))
    )
    (net (code "27") (name "Net-(IC1-BOOT)") (class "Default")
      (node (ref "C5") (pin "2") (pinfunction "2_2") (pintype "passive"))
      (node (ref "IC1") (pin "1") (pinfunction "BOOT_1") (pintype "bidirectional"))
    )
    (net (code "28") (name "Net-(IC1-COMP)") (class "Default")
      (node (ref "C10") (pin "1") (pinfunction "1_1") (pintype "passive"))
      (node (ref "C9") (pin "1") (pinfunction "1_1") (pintype "passive"))
      (node (ref "IC1") (pin "6") (pinfunction "COMP_6") (pintype "bidirectional"))
    )
    (net (code "29") (name "Net-(IC1-EN)") (class "Default")
      (node (ref "IC1") (pin "3") (pinfunction "EN_3") (pintype "bidirectional"))
      (node (ref "R1") (pin "1") (pinfunction "1_1") (pintype "passive"))
      (node (ref "R2") (pin "2") (pinfunction "2_2") (pintype "passive"))
    )
    (net (code "30") (name "Net-(IC1-SS)") (class "Default")
      (node (ref "C4") (pin "1") (pinfunction "1_1") (pintype "passive"))
      (node (ref "IC1") (pin "4") (pinfunction "SS_4") (pintype "bidirectional"))
    )
    (net (code "31") (name "Net-(IC2-BOOT)") (class "Default")
      (node (ref "C15") (pin "2") (pinfunction "2_2") (pintype "passive"))
      (node (ref "IC2") (pin "1") (pinfunction "BOOT_1") (pintype "bidirectional"))
    )
    (net (code "32") (name "Net-(IC2-COMP)") (class "Default")
      (node (ref "C19") (pin "1") (pinfunction "1_1") (pintype "passive"))
      (node (ref "C20") (pin "1") (pinfunction "1_1") (pintype "passive"))
      (node (ref "IC2") (pin "6") (pinfunction "COMP_6") (pintype "bidirectional"))
    )
    (net (code "33") (name "Net-(IC2-EN)") (class "Default")
      (node (ref "IC2") (pin "3") (pinfunction "EN_3") (pintype "bidirectional"))
      (node (ref "R5") (pin "1") (pinfunction "1_1") (pintype "passive"))
      (node (ref "R6") (pin "2") (pinfunction "2_2") (pintype "passive"))
    )
    (net (code "34") (name "Net-(IC2-SS)") (class "Default")
      (node (ref "C14") (pin "1") (pinfunction "1_1") (pintype "passive"))
      (node (ref "IC2") (pin "4") (pinfunction "SS_4") (pintype "bidirectional"))
    )
    (net (code "35") (name "Net-(IC3-BOOT)") (class "Default")
      (node (ref "C25") (pin "2") (pinfunction "2_2") (pintype "passive"))
      (node (ref "IC3") (pin "1") (pinfunction "BOOT_1") (pintype "bidirectional"))
    )
    (net (code "36") (name "Net-(IC3-COMP)") (class "Default")
      (node (ref "C29") (pin "1") (pinfunction "1_1") (pintype "passive"))
      (node (ref "C30") (pin "1") (pinfunction "1_1") (pintype "passive"))
      (node (ref "IC3") (pin "6") (pinfunction "COMP_6") (pintype "bidirectional"))
    )
    (net (code "37") (name "Net-(IC3-EN)") (class "Default")
      (node (ref "IC3") (pin "3") (pinfunction "EN_3") (pintype "bidirectional"))
      (node (ref "R10") (pin "2") (pinfunction "2_2") (pintype "passive"))
      (node (ref "R9") (pin "1") (pinfunction "1_1") (pintype "passive"))
    )
    (net (code "38") (name "Net-(IC3-SS)") (class "Default")
      (node (ref "C24") (pin "1") (pinfunction "1_1") (pintype "passive"))
      (node (ref "IC3") (pin "4") (pinfunction "SS_4") (pintype "bidirectional"))
    )
    (net (code "39") (name "Net-(IC4-BOOT)") (class "Default")
      (node (ref "C35") (pin "2") (pinfunction "2_2") (pintype "passive"))
      (node (ref "IC4") (pin "1") (pinfunction "BOOT_1") (pintype "bidirectional"))
    )
    (net (code "40") (name "Net-(IC4-COMP)") (class "Default")
      (node (ref "C39") (pin "1") (pinfunction "1_1") (pintype "passive"))
      (node (ref "C40") (pin "1") (pinfunction "1_1") (pintype "passive"))
      (node (ref "IC4") (pin "6") (pinfunction "COMP_6") (pintype "bidirectional"))
    )
    (net (code "41") (name "Net-(IC4-EN)") (class "Default")
      (node (ref "IC4") (pin "3") (pinfunction "EN_3") (pintype "bidirectional"))
      (node (ref "R13") (pin "1") (pinfunction "1_1") (pintype "passive"))
      (node (ref "R14") (pin "2") (pinfunction "2_2") (pintype "passive"))
    )
    (net (code "42") (name "Net-(IC4-SS)") (class "Default")
      (node (ref "C34") (pin "1") (pinfunction "1_1") (pintype "passive"))
      (node (ref "IC4") (pin "4") (pinfunction "SS_4") (pintype "bidirectional"))
    )
    (net (code "43") (name "Net-(IC5-BOOT)") (class "Default")
      (node (ref "C45") (pin "2") (pinfunction "2_2") (pintype "passive"))
      (node (ref "IC5") (pin "1") (pinfunction "BOOT_1") (pintype "bidirectional"))
    )
    (net (code "44") (name "Net-(IC5-COMP)") (class "Default")
      (node (ref "C49") (pin "1") (pinfunction "1_1") (pintype "passive"))
      (node (ref "C50") (pin "1") (pinfunction "1_1") (pintype "passive"))
      (node (ref "IC5") (pin "6") (pinfunction "COMP_6") (pintype "bidirectional"))
    )
    (net (code "45") (name "Net-(IC5-EN)") (class "Default")
      (node (ref "IC5") (pin "3") (pinfunction "EN_3") (pintype "bidirectional"))
      (node (ref "R17") (pin "1") (pinfunction "1_1") (pintype "passive"))
      (node (ref "R18") (pin "2") (pinfunction "2_2") (pintype "passive"))
    )
    (net (code "46") (name "Net-(IC5-SS)") (class "Default")
      (node (ref "C44") (pin "1") (pinfunction "1_1") (pintype "passive"))
      (node (ref "IC5") (pin "4") (pinfunction "SS_4") (pintype "bidirectional"))
    )
    (net (code "47") (name "Net-(IC6-BOOT)") (class "Default")
      (node (ref "C55") (pin "2") (pinfunction "2_2") (pintype "passive"))
      (node (ref "IC6") (pin "1") (pinfunction "BOOT_1") (pintype "bidirectional"))
    )
    (net (code "48") (name "Net-(IC6-COMP)") (class "Default")
      (node (ref "C59") (pin "1") (pinfunction "1_1") (pintype "passive"))
      (node (ref "C60") (pin "1") (pinfunction "1_1") (pintype "passive"))
      (node (ref "IC6") (pin "6") (pinfunction "COMP_6") (pintype "bidirectional"))
    )
    (net (code "49") (name "Net-(IC6-EN)") (class "Default")
      (node (ref "IC6") (pin "3") (pinfunction "EN_3") (pintype "bidirectional"))
      (node (ref "R21") (pin "1") (pinfunction "1_1") (pintype "passive"))
      (node (ref "R22") (pin "2") (pinfunction "2_2") (pintype "passive"))
    )
    (net (code "50") (name "Net-(IC6-SS)") (class "Default")
      (node (ref "C54") (pin "1") (pinfunction "1_1") (pintype "passive"))
      (node (ref "IC6") (pin "4") (pinfunction "SS_4") (pintype "bidirectional"))
    )
    (net (code "51") (name "Net-(LED1-PadA)") (class "Default")
      (node (ref "LED1") (pin "A") (pinfunction "A_A") (pintype "passive"))
      (node (ref "R4") (pin "1") (pinfunction "1_1") (pintype "passive"))
    )
    (net (code "52") (name "Net-(LED2-PadA)") (class "Default")
      (node (ref "LED2") (pin "A") (pinfunction "A_A") (pintype "passive"))
      (node (ref "R8") (pin "1") (pinfunction "1_1") (pintype "passive"))
    )
    (net (code "53") (name "Net-(LED3-PadA)") (class "Default")
      (node (ref "LED3") (pin "A") (pinfunction "A_A") (pintype "passive"))
      (node (ref "R12") (pin "1") (pinfunction "1_1") (pintype "passive"))
    )
    (net (code "54") (name "Net-(LED4-PadA)") (class "Default")
      (node (ref "LED4") (pin "A") (pinfunction "A_A") (pintype "passive"))
      (node (ref "R16") (pin "1") (pinfunction "1_1") (pintype "passive"))
    )
    (net (code "55") (name "Net-(LED5-PadA)") (class "Default")
      (node (ref "LED5") (pin "A") (pinfunction "A_A") (pintype "passive"))
      (node (ref "R20") (pin "1") (pinfunction "1_1") (pintype "passive"))
    )
    (net (code "56") (name "Net-(LED6-PadA)") (class "Default")
      (node (ref "LED6") (pin "A") (pinfunction "A_A") (pintype "passive"))
      (node (ref "R24") (pin "1") (pinfunction "1_1") (pintype "passive"))
    )
  )
)
